# AmpPCB.net
KiCad netlist of a schematic drawn in EAGLE
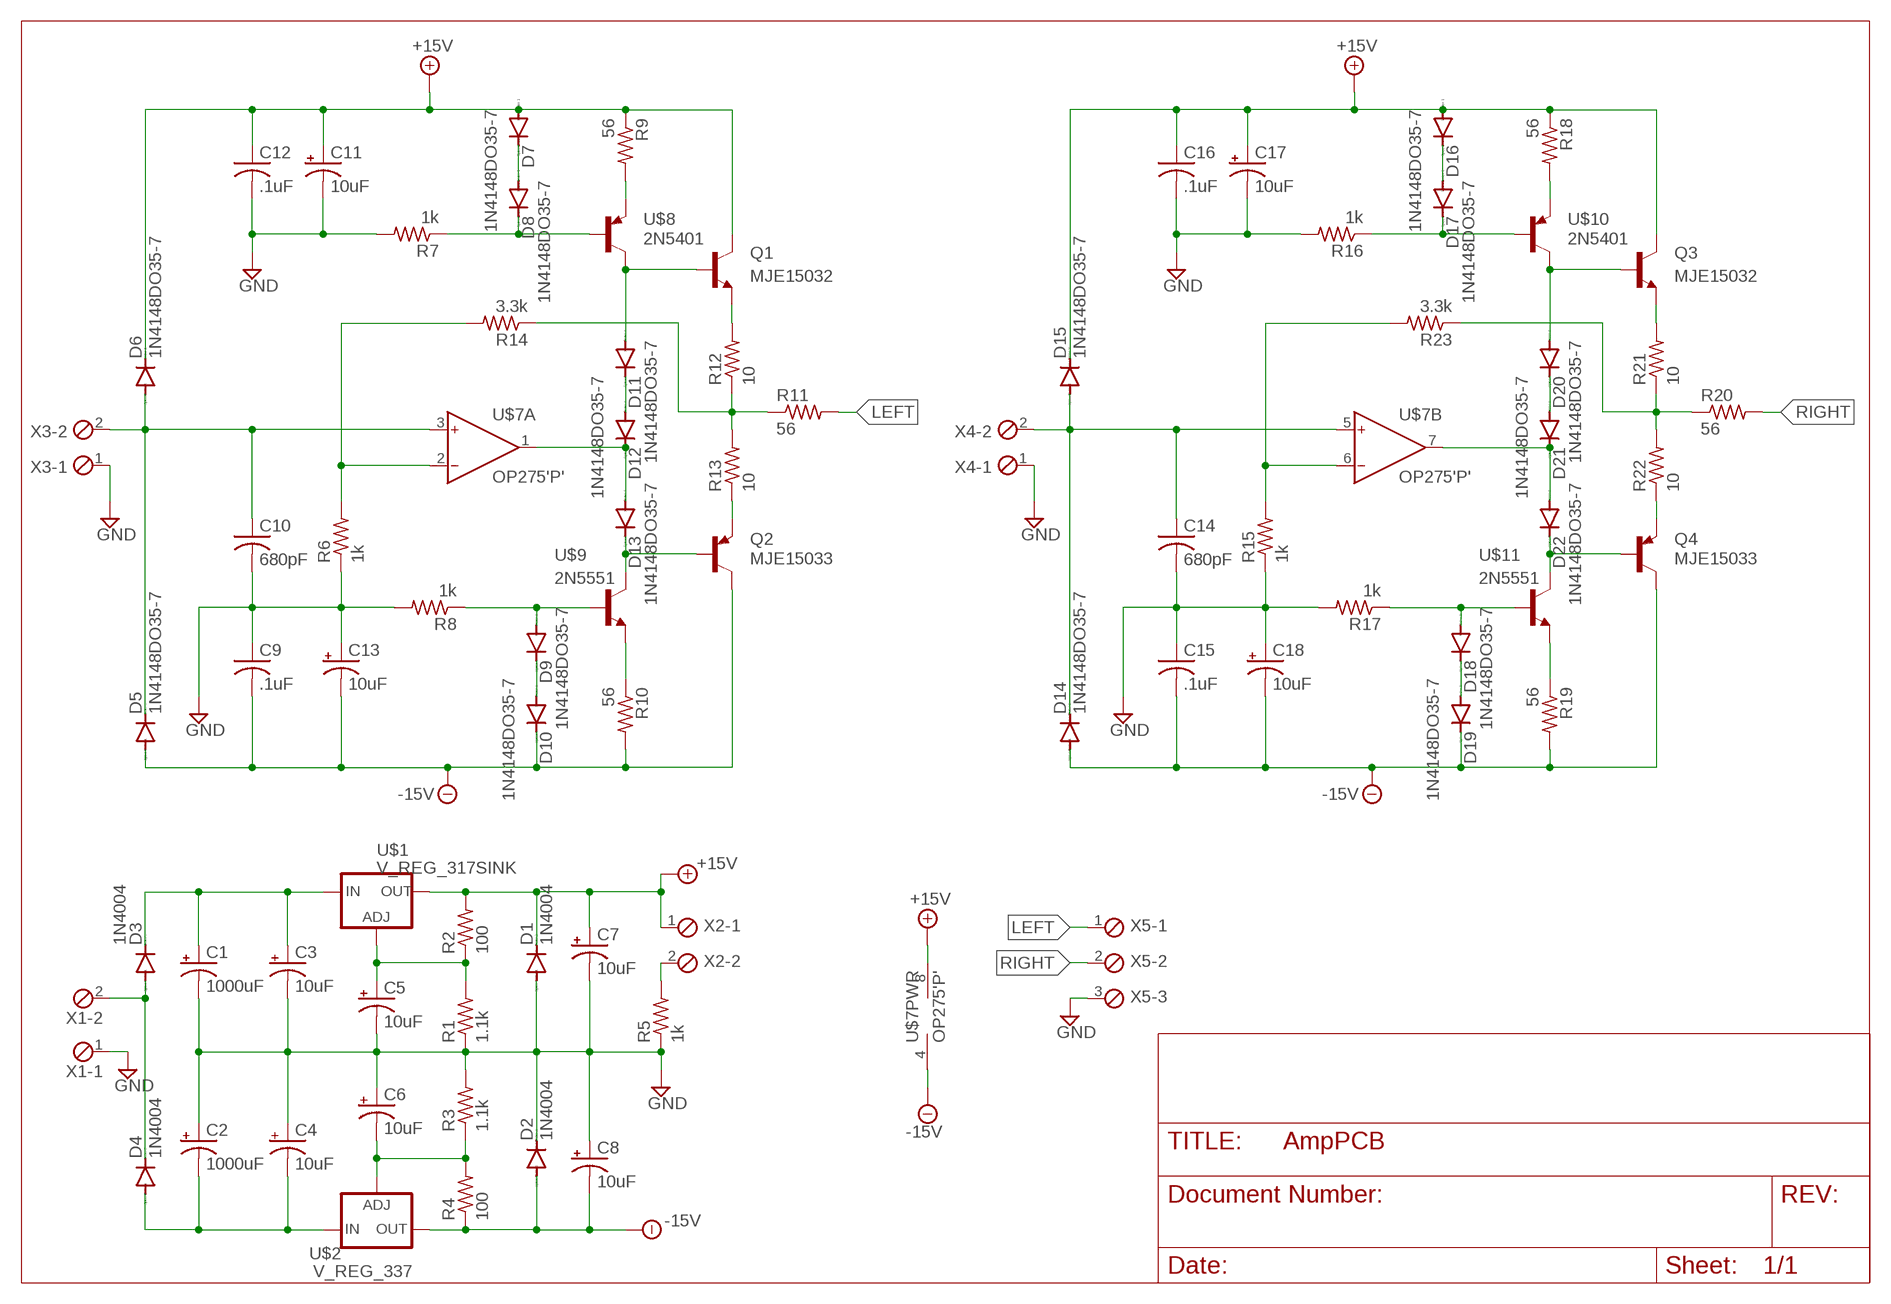
[diagram p0: schematic, sheet 1]

(export (version "E")
  (design (tool "Eeschema 10.0.6"))
  (components
    (comp (ref "C1")
      (value "1000uF")
      (footprint "eagle-import:TT5D10")
      (libsource (lib "eagle-import") (part "CPOL-USTT5D10"))
    )
    (comp (ref "C2")
      (value "1000uF")
      (footprint "eagle-import:TT5D10")
      (libsource (lib "eagle-import") (part "CPOL-USTT5D10"))
    )
    (comp (ref "C3")
      (value "10uF")
      (footprint "eagle-import:E2-5")
      (libsource (lib "eagle-import") (part "CPOL-USE2-5"))
    )
    (comp (ref "C4")
      (value "10uF")
      (footprint "eagle-import:E2-5")
      (libsource (lib "eagle-import") (part "CPOL-USE2-5"))
    )
    (comp (ref "C5")
      (value "10uF")
      (footprint "eagle-import:E2-5")
      (libsource (lib "eagle-import") (part "CPOL-USE2-5"))
    )
    (comp (ref "C6")
      (value "10uF")
      (footprint "eagle-import:E2-5")
      (libsource (lib "eagle-import") (part "CPOL-USE2-5"))
    )
    (comp (ref "C7")
      (value "10uF")
      (footprint "eagle-import:E2-5")
      (libsource (lib "eagle-import") (part "CPOL-USE2-5"))
    )
    (comp (ref "C8")
      (value "10uF")
      (footprint "eagle-import:E2-5")
      (libsource (lib "eagle-import") (part "CPOL-USE2-5"))
    )
    (comp (ref "C9")
      (value ".1uF")
      (footprint "eagle-import:C102-064X133")
      (libsource (lib "eagle-import") (part "C-US102-064X133"))
    )
    (comp (ref "C10")
      (value "680pF")
      (footprint "eagle-import:C075-042X103")
      (libsource (lib "eagle-import") (part "C-US075-042X103"))
    )
    (comp (ref "C11")
      (value "10uF")
      (footprint "eagle-import:E2-5")
      (libsource (lib "eagle-import") (part "CPOL-USE2-5"))
    )
    (comp (ref "C12")
      (value ".1uF")
      (footprint "eagle-import:C102-064X133")
      (libsource (lib "eagle-import") (part "C-US102-064X133"))
    )
    (comp (ref "C13")
      (value "10uF")
      (footprint "eagle-import:E2-5")
      (libsource (lib "eagle-import") (part "CPOL-USE2-5"))
    )
    (comp (ref "C14")
      (value "680pF")
      (footprint "eagle-import:C075-042X103")
      (libsource (lib "eagle-import") (part "C-US075-042X103"))
    )
    (comp (ref "C15")
      (value ".1uF")
      (footprint "eagle-import:C102-064X133")
      (libsource (lib "eagle-import") (part "C-US102-064X133"))
    )
    (comp (ref "C16")
      (value ".1uF")
      (footprint "eagle-import:C102-064X133")
      (libsource (lib "eagle-import") (part "C-US102-064X133"))
    )
    (comp (ref "C17")
      (value "10uF")
      (footprint "eagle-import:E2-5")
      (libsource (lib "eagle-import") (part "CPOL-USE2-5"))
    )
    (comp (ref "C18")
      (value "10uF")
      (footprint "eagle-import:E2-5")
      (libsource (lib "eagle-import") (part "CPOL-USE2-5"))
    )
    (comp (ref "D1")
      (value "1N4004")
      (footprint "eagle-import:DO41-10")
      (libsource (lib "eagle-import") (part "1N4004"))
    )
    (comp (ref "D2")
      (value "1N4004")
      (footprint "eagle-import:DO41-10")
      (libsource (lib "eagle-import") (part "1N4004"))
    )
    (comp (ref "D3")
      (value "1N4004")
      (footprint "eagle-import:DO41-10")
      (libsource (lib "eagle-import") (part "1N4004"))
    )
    (comp (ref "D4")
      (value "1N4004")
      (footprint "eagle-import:DO41-10")
      (libsource (lib "eagle-import") (part "1N4004"))
    )
    (comp (ref "D5")
      (value "1N4148DO35-7")
      (footprint "eagle-import:DO35-7")
      (libsource (lib "eagle-import") (part "1N4148DO35-7"))
    )
    (comp (ref "D6")
      (value "1N4148DO35-7")
      (footprint "eagle-import:DO35-7")
      (libsource (lib "eagle-import") (part "1N4148DO35-7"))
    )
    (comp (ref "D7")
      (value "1N4148DO35-7")
      (footprint "eagle-import:DO35-7")
      (libsource (lib "eagle-import") (part "1N4148DO35-7"))
    )
    (comp (ref "D8")
      (value "1N4148DO35-7")
      (footprint "eagle-import:DO35-7")
      (libsource (lib "eagle-import") (part "1N4148DO35-7"))
    )
    (comp (ref "D9")
      (value "1N4148DO35-7")
      (footprint "eagle-import:DO35-7")
      (libsource (lib "eagle-import") (part "1N4148DO35-7"))
    )
    (comp (ref "D10")
      (value "1N4148DO35-7")
      (footprint "eagle-import:DO35-7")
      (libsource (lib "eagle-import") (part "1N4148DO35-7"))
    )
    (comp (ref "D11")
      (value "1N4148DO35-7")
      (footprint "eagle-import:DO35-7")
      (libsource (lib "eagle-import") (part "1N4148DO35-7"))
    )
    (comp (ref "D12")
      (value "1N4148DO35-7")
      (footprint "eagle-import:DO35-7")
      (libsource (lib "eagle-import") (part "1N4148DO35-7"))
    )
    (comp (ref "D13")
      (value "1N4148DO35-7")
      (footprint "eagle-import:DO35-7")
      (libsource (lib "eagle-import") (part "1N4148DO35-7"))
    )
    (comp (ref "D14")
      (value "1N4148DO35-7")
      (footprint "eagle-import:DO35-7")
      (libsource (lib "eagle-import") (part "1N4148DO35-7"))
    )
    (comp (ref "D15")
      (value "1N4148DO35-7")
      (footprint "eagle-import:DO35-7")
      (libsource (lib "eagle-import") (part "1N4148DO35-7"))
    )
    (comp (ref "D16")
      (value "1N4148DO35-7")
      (footprint "eagle-import:DO35-7")
      (libsource (lib "eagle-import") (part "1N4148DO35-7"))
    )
    (comp (ref "D17")
      (value "1N4148DO35-7")
      (footprint "eagle-import:DO35-7")
      (libsource (lib "eagle-import") (part "1N4148DO35-7"))
    )
    (comp (ref "D18")
      (value "1N4148DO35-7")
      (footprint "eagle-import:DO35-7")
      (libsource (lib "eagle-import") (part "1N4148DO35-7"))
    )
    (comp (ref "D19")
      (value "1N4148DO35-7")
      (footprint "eagle-import:DO35-7")
      (libsource (lib "eagle-import") (part "1N4148DO35-7"))
    )
    (comp (ref "D20")
      (value "1N4148DO35-7")
      (footprint "eagle-import:DO35-7")
      (libsource (lib "eagle-import") (part "1N4148DO35-7"))
    )
    (comp (ref "D21")
      (value "1N4148DO35-7")
      (footprint "eagle-import:DO35-7")
      (libsource (lib "eagle-import") (part "1N4148DO35-7"))
    )
    (comp (ref "D22")
      (value "1N4148DO35-7")
      (footprint "eagle-import:DO35-7")
      (libsource (lib "eagle-import") (part "1N4148DO35-7"))
    )
    (comp (ref "Q1")
      (value "MJE15032")
      (footprint "eagle-import:TO220V")
      (libsource (lib "eagle-import") (part "MJE15032"))
    )
    (comp (ref "Q2")
      (value "MJE15033")
      (footprint "eagle-import:TO220V")
      (libsource (lib "eagle-import") (part "MJE15033"))
    )
    (comp (ref "Q3")
      (value "MJE15032")
      (footprint "eagle-import:TO220V")
      (libsource (lib "eagle-import") (part "MJE15032"))
    )
    (comp (ref "Q4")
      (value "MJE15033")
      (footprint "eagle-import:TO220V")
      (libsource (lib "eagle-import") (part "MJE15033"))
    )
    (comp (ref "R1")
      (value "1.1k")
      (footprint "eagle-import:0207_10")
      (libsource (lib "eagle-import") (part "R-US_0207/10"))
    )
    (comp (ref "R2")
      (value "100")
      (footprint "eagle-import:0207_10")
      (libsource (lib "eagle-import") (part "R-US_0207/10"))
    )
    (comp (ref "R3")
      (value "1.1k")
      (footprint "eagle-import:0207_10")
      (libsource (lib "eagle-import") (part "R-US_0207/10"))
    )
    (comp (ref "R4")
      (value "100")
      (footprint "eagle-import:0207_10")
      (libsource (lib "eagle-import") (part "R-US_0207/10"))
    )
    (comp (ref "R5")
      (value "1k")
      (footprint "eagle-import:0207_10")
      (libsource (lib "eagle-import") (part "R-US_0207/10"))
    )
    (comp (ref "R6")
      (value "1k")
      (footprint "eagle-import:0207_10")
      (libsource (lib "eagle-import") (part "R-US_0207/10"))
    )
    (comp (ref "R7")
      (value "1k")
      (footprint "eagle-import:0207_10")
      (libsource (lib "eagle-import") (part "R-US_0207/10"))
    )
    (comp (ref "R8")
      (value "1k")
      (footprint "eagle-import:0207_10")
      (libsource (lib "eagle-import") (part "R-US_0207/10"))
    )
    (comp (ref "R9")
      (value "56")
      (footprint "eagle-import:0207_10")
      (libsource (lib "eagle-import") (part "R-US_0207/10"))
    )
    (comp (ref "R10")
      (value "56")
      (footprint "eagle-import:0207_10")
      (libsource (lib "eagle-import") (part "R-US_0207/10"))
    )
    (comp (ref "R11")
      (value "56")
      (footprint "eagle-import:0207_10")
      (libsource (lib "eagle-import") (part "R-US_0207/10"))
    )
    (comp (ref "R12")
      (value "10")
      (footprint "eagle-import:0207_10")
      (libsource (lib "eagle-import") (part "R-US_0207/10"))
    )
    (comp (ref "R13")
      (value "10")
      (footprint "eagle-import:0207_10")
      (libsource (lib "eagle-import") (part "R-US_0207/10"))
    )
    (comp (ref "R14")
      (value "3.3k")
      (footprint "eagle-import:0207_10")
      (libsource (lib "eagle-import") (part "R-US_0207/10"))
    )
    (comp (ref "R15")
      (value "1k")
      (footprint "eagle-import:0207_10")
      (libsource (lib "eagle-import") (part "R-US_0207/10"))
    )
    (comp (ref "R16")
      (value "1k")
      (footprint "eagle-import:0207_10")
      (libsource (lib "eagle-import") (part "R-US_0207/10"))
    )
    (comp (ref "R17")
      (value "1k")
      (footprint "eagle-import:0207_10")
      (libsource (lib "eagle-import") (part "R-US_0207/10"))
    )
    (comp (ref "R18")
      (value "56")
      (footprint "eagle-import:0207_10")
      (libsource (lib "eagle-import") (part "R-US_0207/10"))
    )
    (comp (ref "R19")
      (value "56")
      (footprint "eagle-import:0207_10")
      (libsource (lib "eagle-import") (part "R-US_0207/10"))
    )
    (comp (ref "R20")
      (value "56")
      (footprint "eagle-import:0207_10")
      (libsource (lib "eagle-import") (part "R-US_0207/10"))
    )
    (comp (ref "R21")
      (value "10")
      (footprint "eagle-import:0207_10")
      (libsource (lib "eagle-import") (part "R-US_0207/10"))
    )
    (comp (ref "R22")
      (value "10")
      (footprint "eagle-import:0207_10")
      (libsource (lib "eagle-import") (part "R-US_0207/10"))
    )
    (comp (ref "R23")
      (value "3.3k")
      (footprint "eagle-import:0207_10")
      (libsource (lib "eagle-import") (part "R-US_0207/10"))
    )
    (comp (ref "U$1")
      (value "V_REG_317SINK")
      (footprint "eagle-import:TO220-ADJ")
      (libsource (lib "eagle-import") (part "V_REG_317SINK"))
    )
    (comp (ref "U$2")
      (value "V_REG_337")
      (footprint "eagle-import:TO220-ADJ-NEG")
      (libsource (lib "eagle-import") (part "V_REG_337"))
    )
    (comp (ref "U$7")
      (value "OP275'P'")
      (footprint "eagle-import:DIL08")
      (libsource (lib "eagle-import") (part "OP275'P'"))
    )
    (comp (ref "U$8")
      (value "2N5401")
      (footprint "eagle-import:2N5401")
      (libsource (lib "eagle-import") (part "2N5401"))
    )
    (comp (ref "U$9")
      (value "2N5551")
      (footprint "eagle-import:2N5551")
      (libsource (lib "eagle-import") (part "2N5551"))
    )
    (comp (ref "U$10")
      (value "2N5401")
      (footprint "eagle-import:2N5401")
      (libsource (lib "eagle-import") (part "2N5401"))
    )
    (comp (ref "U$11")
      (value "2N5551")
      (footprint "eagle-import:2N5551")
      (libsource (lib "eagle-import") (part "2N5551"))
    )
    (comp (ref "X1")
      (value "MPT2")
      (footprint "eagle-import:2POL254")
      (libsource (lib "eagle-import") (part "MPT2"))
    )
    (comp (ref "X2")
      (value "MPT2")
      (footprint "eagle-import:2POL254")
      (libsource (lib "eagle-import") (part "MPT2"))
    )
    (comp (ref "X3")
      (value "MPT2")
      (footprint "eagle-import:2POL254")
      (libsource (lib "eagle-import") (part "MPT2"))
    )
    (comp (ref "X4")
      (value "MPT2")
      (footprint "eagle-import:2POL254")
      (libsource (lib "eagle-import") (part "MPT2"))
    )
    (comp (ref "X5")
      (value "MPT3")
      (footprint "eagle-import:3POL254")
      (libsource (lib "eagle-import") (part "MPT3"))
    )
  )
  (nets
    (net (code "1") (name "+15V") (class "Default")
      (node (ref "C11") (pin "+") (pinfunction "+_+") (pintype "passive"))
      (node (ref "C12") (pin "1") (pinfunction "1_1") (pintype "passive"))
      (node (ref "C16") (pin "1") (pinfunction "1_1") (pintype "passive"))
      (node (ref "C17") (pin "+") (pinfunction "+_+") (pintype "passive"))
      (node (ref "C7") (pin "+") (pinfunction "+_+") (pintype "passive"))
      (node (ref "D1") (pin "C") (pinfunction "C_C") (pintype "passive"))
      (node (ref "D15") (pin "C") (pinfunction "C_C") (pintype "passive"))
      (node (ref "D16") (pin "A") (pinfunction "A_A") (pintype "passive"))
      (node (ref "D6") (pin "C") (pinfunction "C_C") (pintype "passive"))
      (node (ref "D7") (pin "A") (pinfunction "A_A") (pintype "passive"))
      (node (ref "Q1") (pin "2") (pinfunction "C_2") (pintype "passive"))
      (node (ref "Q3") (pin "2") (pinfunction "C_2") (pintype "passive"))
      (node (ref "R18") (pin "1") (pinfunction "1_1") (pintype "passive"))
      (node (ref "R2") (pin "2") (pinfunction "2_2") (pintype "passive"))
      (node (ref "R9") (pin "1") (pinfunction "1_1") (pintype "passive"))
      (node (ref "U$1") (pin "OUT") (pinfunction "OUT_OUT") (pintype "output"))
      (node (ref "U$7") (pin "8") (pinfunction "V+_8") (pintype "power_in"))
      (node (ref "X2") (pin "1") (pinfunction "1_1") (pintype "passive"))
    )
    (net (code "2") (name "-15V") (class "Default")
      (node (ref "C13") (pin "-") (pinfunction "-_-") (pintype "passive"))
      (node (ref "C15") (pin "2") (pinfunction "2_2") (pintype "passive"))
      (node (ref "C18") (pin "-") (pinfunction "-_-") (pintype "passive"))
      (node (ref "C8") (pin "-") (pinfunction "-_-") (pintype "passive"))
      (node (ref "C9") (pin "2") (pinfunction "2_2") (pintype "passive"))
      (node (ref "D10") (pin "C") (pinfunction "C_C") (pintype "passive"))
      (node (ref "D14") (pin "A") (pinfunction "A_A") (pintype "passive"))
      (node (ref "D19") (pin "C") (pinfunction "C_C") (pintype "passive"))
      (node (ref "D2") (pin "A") (pinfunction "A_A") (pintype "passive"))
      (node (ref "D5") (pin "A") (pinfunction "A_A") (pintype "passive"))
      (node (ref "Q2") (pin "2") (pinfunction "C_2") (pintype "passive"))
      (node (ref "Q4") (pin "2") (pinfunction "C_2") (pintype "passive"))
      (node (ref "R10") (pin "2") (pinfunction "2_2") (pintype "passive"))
      (node (ref "R19") (pin "2") (pinfunction "2_2") (pintype "passive"))
      (node (ref "R4") (pin "1") (pinfunction "1_1") (pintype "passive"))
      (node (ref "U$2") (pin "OUT") (pinfunction "OUT_OUT") (pintype "output"))
      (node (ref "U$7") (pin "4") (pinfunction "V-_4") (pintype "power_in"))
    )
    (net (code "3") (name "GND") (class "Default")
      (node (ref "C1") (pin "-") (pinfunction "-_-") (pintype "passive"))
      (node (ref "C10") (pin "2") (pinfunction "2_2") (pintype "passive"))
      (node (ref "C11") (pin "-") (pinfunction "-_-") (pintype "passive"))
      (node (ref "C12") (pin "2") (pinfunction "2_2") (pintype "passive"))
      (node (ref "C13") (pin "+") (pinfunction "+_+") (pintype "passive"))
      (node (ref "C14") (pin "2") (pinfunction "2_2") (pintype "passive"))
      (node (ref "C15") (pin "1") (pinfunction "1_1") (pintype "passive"))
      (node (ref "C16") (pin "2") (pinfunction "2_2") (pintype "passive"))
      (node (ref "C17") (pin "-") (pinfunction "-_-") (pintype "passive"))
      (node (ref "C18") (pin "+") (pinfunction "+_+") (pintype "passive"))
      (node (ref "C2") (pin "+") (pinfunction "+_+") (pintype "passive"))
      (node (ref "C3") (pin "-") (pinfunction "-_-") (pintype "passive"))
      (node (ref "C4") (pin "+") (pinfunction "+_+") (pintype "passive"))
      (node (ref "C5") (pin "-") (pinfunction "-_-") (pintype "passive"))
      (node (ref "C6") (pin "+") (pinfunction "+_+") (pintype "passive"))
      (node (ref "C7") (pin "-") (pinfunction "-_-") (pintype "passive"))
      (node (ref "C8") (pin "+") (pinfunction "+_+") (pintype "passive"))
      (node (ref "C9") (pin "1") (pinfunction "1_1") (pintype "passive"))
      (node (ref "D1") (pin "A") (pinfunction "A_A") (pintype "passive"))
      (node (ref "D2") (pin "C") (pinfunction "C_C") (pintype "passive"))
      (node (ref "R1") (pin "1") (pinfunction "1_1") (pintype "passive"))
      (node (ref "R15") (pin "1") (pinfunction "1_1") (pintype "passive"))
      (node (ref "R16") (pin "2") (pinfunction "2_2") (pintype "passive"))
      (node (ref "R17") (pin "2") (pinfunction "2_2") (pintype "passive"))
      (node (ref "R3") (pin "2") (pinfunction "2_2") (pintype "passive"))
      (node (ref "R5") (pin "1") (pinfunction "1_1") (pintype "passive"))
      (node (ref "R6") (pin "1") (pinfunction "1_1") (pintype "passive"))
      (node (ref "R7") (pin "2") (pinfunction "2_2") (pintype "passive"))
      (node (ref "R8") (pin "2") (pinfunction "2_2") (pintype "passive"))
      (node (ref "X1") (pin "1") (pinfunction "1_1") (pintype "passive"))
      (node (ref "X3") (pin "1") (pinfunction "1_1") (pintype "passive"))
      (node (ref "X4") (pin "1") (pinfunction "1_1") (pintype "passive"))
      (node (ref "X5") (pin "3") (pinfunction "1_3") (pintype "passive"))
    )
    (net (code "4") (name "LEFT") (class "Default")
      (node (ref "R11") (pin "2") (pinfunction "2_2") (pintype "passive"))
      (node (ref "X5") (pin "1") (pinfunction "1_1") (pintype "passive"))
    )
    (net (code "5") (name "Net-(C1-Pad+)") (class "Default")
      (node (ref "C1") (pin "+") (pinfunction "+_+") (pintype "passive"))
      (node (ref "C3") (pin "+") (pinfunction "+_+") (pintype "passive"))
      (node (ref "D3") (pin "C") (pinfunction "C_C") (pintype "passive"))
      (node (ref "U$1") (pin "IN") (pinfunction "IN_IN") (pintype "input"))
    )
    (net (code "6") (name "Net-(C2-Pad-)") (class "Default")
      (node (ref "C2") (pin "-") (pinfunction "-_-") (pintype "passive"))
      (node (ref "C4") (pin "-") (pinfunction "-_-") (pintype "passive"))
      (node (ref "D4") (pin "A") (pinfunction "A_A") (pintype "passive"))
      (node (ref "U$2") (pin "IN") (pinfunction "IN_IN") (pintype "input"))
    )
    (net (code "7") (name "Net-(C5-Pad+)") (class "Default")
      (node (ref "C5") (pin "+") (pinfunction "+_+") (pintype "passive"))
      (node (ref "R1") (pin "2") (pinfunction "2_2") (pintype "passive"))
      (node (ref "R2") (pin "1") (pinfunction "1_1") (pintype "passive"))
      (node (ref "U$1") (pin "ADJ") (pinfunction "ADJ_ADJ") (pintype "input"))
    )
    (net (code "8") (name "Net-(C6-Pad-)") (class "Default")
      (node (ref "C6") (pin "-") (pinfunction "-_-") (pintype "passive"))
      (node (ref "R3") (pin "1") (pinfunction "1_1") (pintype "passive"))
      (node (ref "R4") (pin "2") (pinfunction "2_2") (pintype "passive"))
      (node (ref "U$2") (pin "ADJ") (pinfunction "ADJ_ADJ") (pintype "input"))
    )
    (net (code "9") (name "Net-(D7-PadC)") (class "Default")
      (node (ref "D7") (pin "C") (pinfunction "C_C") (pintype "passive"))
      (node (ref "D8") (pin "A") (pinfunction "A_A") (pintype "passive"))
    )
    (net (code "10") (name "Net-(D8-PadC)") (class "Default")
      (node (ref "D8") (pin "C") (pinfunction "C_C") (pintype "passive"))
      (node (ref "R7") (pin "1") (pinfunction "1_1") (pintype "passive"))
      (node (ref "U$8") (pin "B") (pinfunction "B_B") (pintype "passive"))
    )
    (net (code "11") (name "Net-(D9-PadA)") (class "Default")
      (node (ref "D9") (pin "A") (pinfunction "A_A") (pintype "passive"))
      (node (ref "R8") (pin "1") (pinfunction "1_1") (pintype "passive"))
      (node (ref "U$9") (pin "B") (pinfunction "B_B") (pintype "passive"))
    )
    (net (code "12") (name "Net-(D10-PadA)") (class "Default")
      (node (ref "D10") (pin "A") (pinfunction "A_A") (pintype "passive"))
      (node (ref "D9") (pin "C") (pinfunction "C_C") (pintype "passive"))
    )
    (net (code "13") (name "Net-(D11-PadC)") (class "Default")
      (node (ref "D11") (pin "C") (pinfunction "C_C") (pintype "passive"))
      (node (ref "D12") (pin "A") (pinfunction "A_A") (pintype "passive"))
    )
    (net (code "14") (name "Net-(D16-PadC)") (class "Default")
      (node (ref "D16") (pin "C") (pinfunction "C_C") (pintype "passive"))
      (node (ref "D17") (pin "A") (pinfunction "A_A") (pintype "passive"))
    )
    (net (code "15") (name "Net-(D17-PadC)") (class "Default")
      (node (ref "D17") (pin "C") (pinfunction "C_C") (pintype "passive"))
      (node (ref "R16") (pin "1") (pinfunction "1_1") (pintype "passive"))
      (node (ref "U$10") (pin "B") (pinfunction "B_B") (pintype "passive"))
    )
    (net (code "16") (name "Net-(D18-PadA)") (class "Default")
      (node (ref "D18") (pin "A") (pinfunction "A_A") (pintype "passive"))
      (node (ref "R17") (pin "1") (pinfunction "1_1") (pintype "passive"))
      (node (ref "U$11") (pin "B") (pinfunction "B_B") (pintype "passive"))
    )
    (net (code "17") (name "Net-(D18-PadC)") (class "Default")
      (node (ref "D18") (pin "C") (pinfunction "C_C") (pintype "passive"))
      (node (ref "D19") (pin "A") (pinfunction "A_A") (pintype "passive"))
    )
    (net (code "18") (name "Net-(D20-PadC)") (class "Default")
      (node (ref "D20") (pin "C") (pinfunction "C_C") (pintype "passive"))
      (node (ref "D21") (pin "A") (pinfunction "A_A") (pintype "passive"))
    )
    (net (code "19") (name "Net-(Q1-B)") (class "Default")
      (node (ref "D11") (pin "A") (pinfunction "A_A") (pintype "passive"))
      (node (ref "Q1") (pin "1") (pinfunction "B_1") (pintype "passive"))
      (node (ref "U$8") (pin "C") (pinfunction "C_C") (pintype "passive"))
    )
    (net (code "20") (name "Net-(Q1-E)") (class "Default")
      (node (ref "Q1") (pin "3") (pinfunction "E_3") (pintype "passive"))
      (node (ref "R12") (pin "2") (pinfunction "2_2") (pintype "passive"))
    )
    (net (code "21") (name "Net-(Q2-B)") (class "Default")
      (node (ref "D13") (pin "C") (pinfunction "C_C") (pintype "passive"))
      (node (ref "Q2") (pin "1") (pinfunction "B_1") (pintype "passive"))
      (node (ref "U$9") (pin "C") (pinfunction "C_C") (pintype "passive"))
    )
    (net (code "22") (name "Net-(Q2-E)") (class "Default")
      (node (ref "Q2") (pin "3") (pinfunction "E_3") (pintype "passive"))
      (node (ref "R13") (pin "1") (pinfunction "1_1") (pintype "passive"))
    )
    (net (code "23") (name "Net-(Q3-B)") (class "Default")
      (node (ref "D20") (pin "A") (pinfunction "A_A") (pintype "passive"))
      (node (ref "Q3") (pin "1") (pinfunction "B_1") (pintype "passive"))
      (node (ref "U$10") (pin "C") (pinfunction "C_C") (pintype "passive"))
    )
    (net (code "24") (name "Net-(Q3-E)") (class "Default")
      (node (ref "Q3") (pin "3") (pinfunction "E_3") (pintype "passive"))
      (node (ref "R21") (pin "2") (pinfunction "2_2") (pintype "passive"))
    )
    (net (code "25") (name "Net-(Q4-B)") (class "Default")
      (node (ref "D22") (pin "C") (pinfunction "C_C") (pintype "passive"))
      (node (ref "Q4") (pin "1") (pinfunction "B_1") (pintype "passive"))
      (node (ref "U$11") (pin "C") (pinfunction "C_C") (pintype "passive"))
    )
    (net (code "26") (name "Net-(Q4-E)") (class "Default")
      (node (ref "Q4") (pin "3") (pinfunction "E_3") (pintype "passive"))
      (node (ref "R22") (pin "1") (pinfunction "1_1") (pintype "passive"))
    )
    (net (code "27") (name "Net-(R9-Pad2)") (class "Default")
      (node (ref "R9") (pin "2") (pinfunction "2_2") (pintype "passive"))
      (node (ref "U$8") (pin "E") (pinfunction "E_E") (pintype "passive"))
    )
    (net (code "28") (name "Net-(R10-Pad1)") (class "Default")
      (node (ref "R10") (pin "1") (pinfunction "1_1") (pintype "passive"))
      (node (ref "U$9") (pin "E") (pinfunction "E_E") (pintype "passive"))
    )
    (net (code "29") (name "Net-(R11-Pad1)") (class "Default")
      (node (ref "R11") (pin "1") (pinfunction "1_1") (pintype "passive"))
      (node (ref "R12") (pin "1") (pinfunction "1_1") (pintype "passive"))
      (node (ref "R13") (pin "2") (pinfunction "2_2") (pintype "passive"))
      (node (ref "R14") (pin "1") (pinfunction "1_1") (pintype "passive"))
    )
    (net (code "30") (name "Net-(R18-Pad2)") (class "Default")
      (node (ref "R18") (pin "2") (pinfunction "2_2") (pintype "passive"))
      (node (ref "U$10") (pin "E") (pinfunction "E_E") (pintype "passive"))
    )
    (net (code "31") (name "Net-(R19-Pad1)") (class "Default")
      (node (ref "R19") (pin "1") (pinfunction "1_1") (pintype "passive"))
      (node (ref "U$11") (pin "E") (pinfunction "E_E") (pintype "passive"))
    )
    (net (code "32") (name "Net-(R20-Pad1)") (class "Default")
      (node (ref "R20") (pin "1") (pinfunction "1_1") (pintype "passive"))
      (node (ref "R21") (pin "1") (pinfunction "1_1") (pintype "passive"))
      (node (ref "R22") (pin "2") (pinfunction "2_2") (pintype "passive"))
      (node (ref "R23") (pin "1") (pinfunction "1_1") (pintype "passive"))
    )
    (net (code "33") (name "Net-(U$7A-IN+)") (class "Default")
      (node (ref "C10") (pin "1") (pinfunction "1_1") (pintype "passive"))
      (node (ref "D5") (pin "C") (pinfunction "C_C") (pintype "passive"))
      (node (ref "D6") (pin "A") (pinfunction "A_A") (pintype "passive"))
      (node (ref "U$7") (pin "3") (pinfunction "IN+_3") (pintype "input"))
      (node (ref "X3") (pin "2") (pinfunction "1_2") (pintype "passive"))
    )
    (net (code "34") (name "Net-(U$7A-IN-)") (class "Default")
      (node (ref "R14") (pin "2") (pinfunction "2_2") (pintype "passive"))
      (node (ref "R6") (pin "2") (pinfunction "2_2") (pintype "passive"))
      (node (ref "U$7") (pin "2") (pinfunction "IN-_2") (pintype "input"))
    )
    (net (code "35") (name "Net-(U$7A-OUT)") (class "Default")
      (node (ref "D12") (pin "C") (pinfunction "C_C") (pintype "passive"))
      (node (ref "D13") (pin "A") (pinfunction "A_A") (pintype "passive"))
      (node (ref "U$7") (pin "1") (pinfunction "OUT_1") (pintype "output"))
    )
    (net (code "36") (name "Net-(U$7B-IN+)") (class "Default")
      (node (ref "C14") (pin "1") (pinfunction "1_1") (pintype "passive"))
      (node (ref "D14") (pin "C") (pinfunction "C_C") (pintype "passive"))
      (node (ref "D15") (pin "A") (pinfunction "A_A") (pintype "passive"))
      (node (ref "U$7") (pin "5") (pinfunction "IN+_5") (pintype "input"))
      (node (ref "X4") (pin "2") (pinfunction "1_2") (pintype "passive"))
    )
    (net (code "37") (name "Net-(U$7B-IN-)") (class "Default")
      (node (ref "R15") (pin "2") (pinfunction "2_2") (pintype "passive"))
      (node (ref "R23") (pin "2") (pinfunction "2_2") (pintype "passive"))
      (node (ref "U$7") (pin "6") (pinfunction "IN-_6") (pintype "input"))
    )
    (net (code "38") (name "Net-(U$7B-OUT)") (class "Default")
      (node (ref "D21") (pin "C") (pinfunction "C_C") (pintype "passive"))
      (node (ref "D22") (pin "A") (pinfunction "A_A") (pintype "passive"))
      (node (ref "U$7") (pin "7") (pinfunction "OUT_7") (pintype "output"))
    )
    (net (code "39") (name "Net-(X1B-1)") (class "Default")
      (node (ref "D3") (pin "A") (pinfunction "A_A") (pintype "passive"))
      (node (ref "D4") (pin "C") (pinfunction "C_C") (pintype "passive"))
      (node (ref "X1") (pin "2") (pinfunction "1_2") (pintype "passive"))
    )
    (net (code "40") (name "Net-(X2B-1)") (class "Default")
      (node (ref "R5") (pin "2") (pinfunction "2_2") (pintype "passive"))
      (node (ref "X2") (pin "2") (pinfunction "1_2") (pintype "passive"))
    )
    (net (code "41") (name "RIGHT") (class "Default")
      (node (ref "R20") (pin "2") (pinfunction "2_2") (pintype "passive"))
      (node (ref "X5") (pin "2") (pinfunction "1_2") (pintype "passive"))
    )
  )
)
